# SCH.net
KiCad netlist of a schematic drawn in Altium Designer
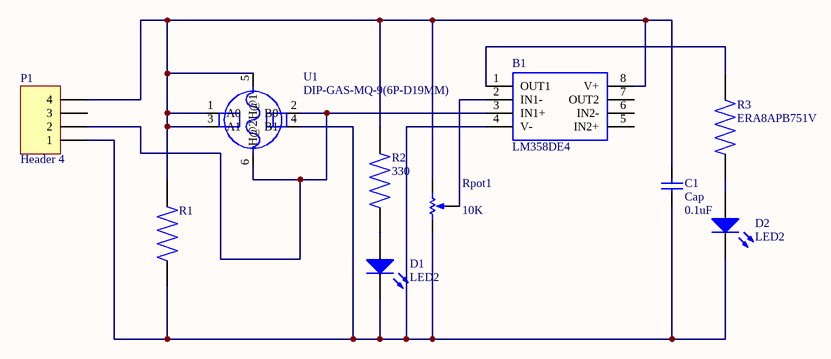
[diagram p0: SCH.SchDoc]

(export (version "E")
  (design (tool "Eeschema 10.0.6"))
  (components
    (comp (ref "B1")
      (value "LM358DE4")
      (footprint "DIP794W45P254L959H508Q8")
      (fields (field (name "MOUSER PART NUMBER") "595-LM358DE4"))
      (libsource (lib "LM358DE4sch") (part "LM358DE4"))
    )
    (comp (ref "C1")
      (value "Cap")
      (footprint "RAD-0.3")
      (description "Capacitor")
      (fields (field (name "ALTIUM_VALUE") "0.1uF") (field (name "PUBLISHER") "Altium Limited"))
      (libsource (lib "Miscellaneous Devices") (part "Cap"))
    )
    (comp (ref "D1")
      (value "LED2")
      (footprint "3.2X1.6X1.1")
      (description "Typical RED, GREEN, YELLOW, AMBER GaAs LED")
      (fields (field (name "PUBLISHER") "Altium Limited"))
      (libsource (lib "Miscellaneous Devices") (part "LED2"))
    )
    (comp (ref "D2")
      (value "LED2")
      (footprint "3.2X1.6X1.1")
      (description "Typical RED, GREEN, YELLOW, AMBER GaAs LED")
      (fields (field (name "PUBLISHER") "Altium Limited"))
      (libsource (lib "Miscellaneous Devices") (part "LED2"))
    )
    (comp (ref "P1")
      (value "Header 4")
      (footprint "HDR1X4")
      (description "Header, 4-Pin")
      (fields (field (name "PUBLISHER") "Altium Limited"))
      (libsource (lib "Miscellaneous Connectors") (part "Header 4"))
    )
    (comp (ref "R1")
      (value "~")
      (footprint "RES_ERA8APB751V")
      (fields (field (name "MP") "ERA8APB751V"))
      (libsource (lib "smd 1206 res") (part "ERA8APB751V"))
    )
    (comp (ref "R2")
      (value "330")
      (footprint "RES_ERA8APB751V")
      (fields (field (name "MP") "ERA8APB751V"))
      (libsource (lib "smd 1206 res") (part "ERA8APB751V"))
    )
    (comp (ref "R3")
      (value "ERA8APB751V")
      (footprint "RES_ERA8APB751V")
      (libsource (lib "smd 1206 res") (part "ERA8APB751V"))
    )
    (comp (ref "Rpot1")
      (value "10K")
      (footprint "VR5")
      (description "Potentiometer")
      (fields (field (name "PUBLISHER") "Altium Limited"))
      (libsource (lib "Miscellaneous Devices") (part "RPot"))
    )
    (comp (ref "U1")
      (value "DIP-GAS-MQ-9(6P-D19MM)")
      (footprint "SNR6-D19.0MM")
      (description "47ÂµF Â±20% 6.3V Ceramic Capacitor X5R 0805 _2012 Metric_")
      (fields (field (name "MF") "Samsung Electro-Mechanics") (field (name "MP") "MQ-9"))
      (libsource (lib "DIP-GAS-MQ-9_6P-D19MM_") (part "DIP-GAS-MQ-9(6P-D19MM)"))
    )
  )
  (nets
    (net (code "1") (name "Net-(B1-IN1+)") (class "Default")
      (node (ref "B1") (pin "3") (pinfunction "IN1+_3") (pintype "passive"))
      (node (ref "P1") (pin "2") (pinfunction "2_2") (pintype "passive"))
      (node (ref "U1") (pin "2") (pinfunction "B0_2") (pintype "bidirectional"))
      (node (ref "U1") (pin "6") (pinfunction "H@2_6") (pintype "bidirectional"))
    )
    (net (code "2") (name "Net-(B1-IN1-)") (class "Default")
      (node (ref "B1") (pin "2") (pinfunction "IN1-_2") (pintype "passive"))
      (node (ref "Rpot1") (pin "3") (pinfunction "TAP_3") (pintype "passive"))
    )
    (net (code "3") (name "Net-(B1-OUT1)") (class "Default")
      (node (ref "B1") (pin "1") (pinfunction "OUT1_1") (pintype "passive"))
      (node (ref "R3") (pin "2") (pinfunction "2_2") (pintype "passive"))
    )
    (net (code "4") (name "Net-(B1-V+)") (class "Default")
      (node (ref "B1") (pin "8") (pinfunction "V+_8") (pintype "passive"))
      (node (ref "C1") (pin "2") (pinfunction "2_2") (pintype "passive"))
      (node (ref "P1") (pin "4") (pinfunction "4_4") (pintype "passive"))
      (node (ref "R1") (pin "2") (pinfunction "2_2") (pintype "passive"))
      (node (ref "R2") (pin "2") (pinfunction "2_2") (pintype "passive"))
      (node (ref "Rpot1") (pin "2") (pinfunction "BOT_2") (pintype "passive"))
      (node (ref "U1") (pin "1") (pinfunction "A0_1") (pintype "bidirectional"))
      (node (ref "U1") (pin "3") (pinfunction "A1_3") (pintype "bidirectional"))
      (node (ref "U1") (pin "5") (pinfunction "H@1_5") (pintype "bidirectional"))
    )
    (net (code "5") (name "Net-(B1-V-)") (class "Default")
      (node (ref "B1") (pin "4") (pinfunction "V-_4") (pintype "passive"))
      (node (ref "C1") (pin "1") (pinfunction "1_1") (pintype "passive"))
      (node (ref "D1") (pin "2") (pinfunction "K_2") (pintype "passive"))
      (node (ref "D2") (pin "2") (pinfunction "K_2") (pintype "passive"))
      (node (ref "P1") (pin "1") (pinfunction "1_1") (pintype "passive"))
      (node (ref "R1") (pin "1") (pinfunction "1_1") (pintype "passive"))
      (node (ref "Rpot1") (pin "1") (pinfunction "TOP_1") (pintype "passive"))
      (node (ref "U1") (pin "4") (pinfunction "B1_4") (pintype "bidirectional"))
    )
    (net (code "6") (name "Net-(D1-A)") (class "Default")
      (node (ref "D1") (pin "1") (pinfunction "A_1") (pintype "passive"))
      (node (ref "R2") (pin "1") (pinfunction "1_1") (pintype "passive"))
    )
    (net (code "7") (name "Net-(D2-A)") (class "Default")
      (node (ref "D2") (pin "1") (pinfunction "A_1") (pintype "passive"))
      (node (ref "R3") (pin "1") (pinfunction "1_1") (pintype "passive"))
    )
    (net (code "8") (name "unconnected-(B1-IN2+-Pad5)") (class "Default")
      (node (ref "B1") (pin "5") (pinfunction "IN2+_5") (pintype "passive"))
    )
    (net (code "9") (name "unconnected-(B1-IN2--Pad6)") (class "Default")
      (node (ref "B1") (pin "6") (pinfunction "IN2-_6") (pintype "passive"))
    )
    (net (code "10") (name "unconnected-(B1-OUT2-Pad7)") (class "Default")
      (node (ref "B1") (pin "7") (pinfunction "OUT2_7") (pintype "passive"))
    )
    (net (code "11") (name "unconnected-(P1-Pad3)") (class "Default")
      (node (ref "P1") (pin "3") (pinfunction "3_3") (pintype "passive"))
    )
  )
)
